# stmbluepill2.net
KiCad netlist of a schematic drawn in EAGLE
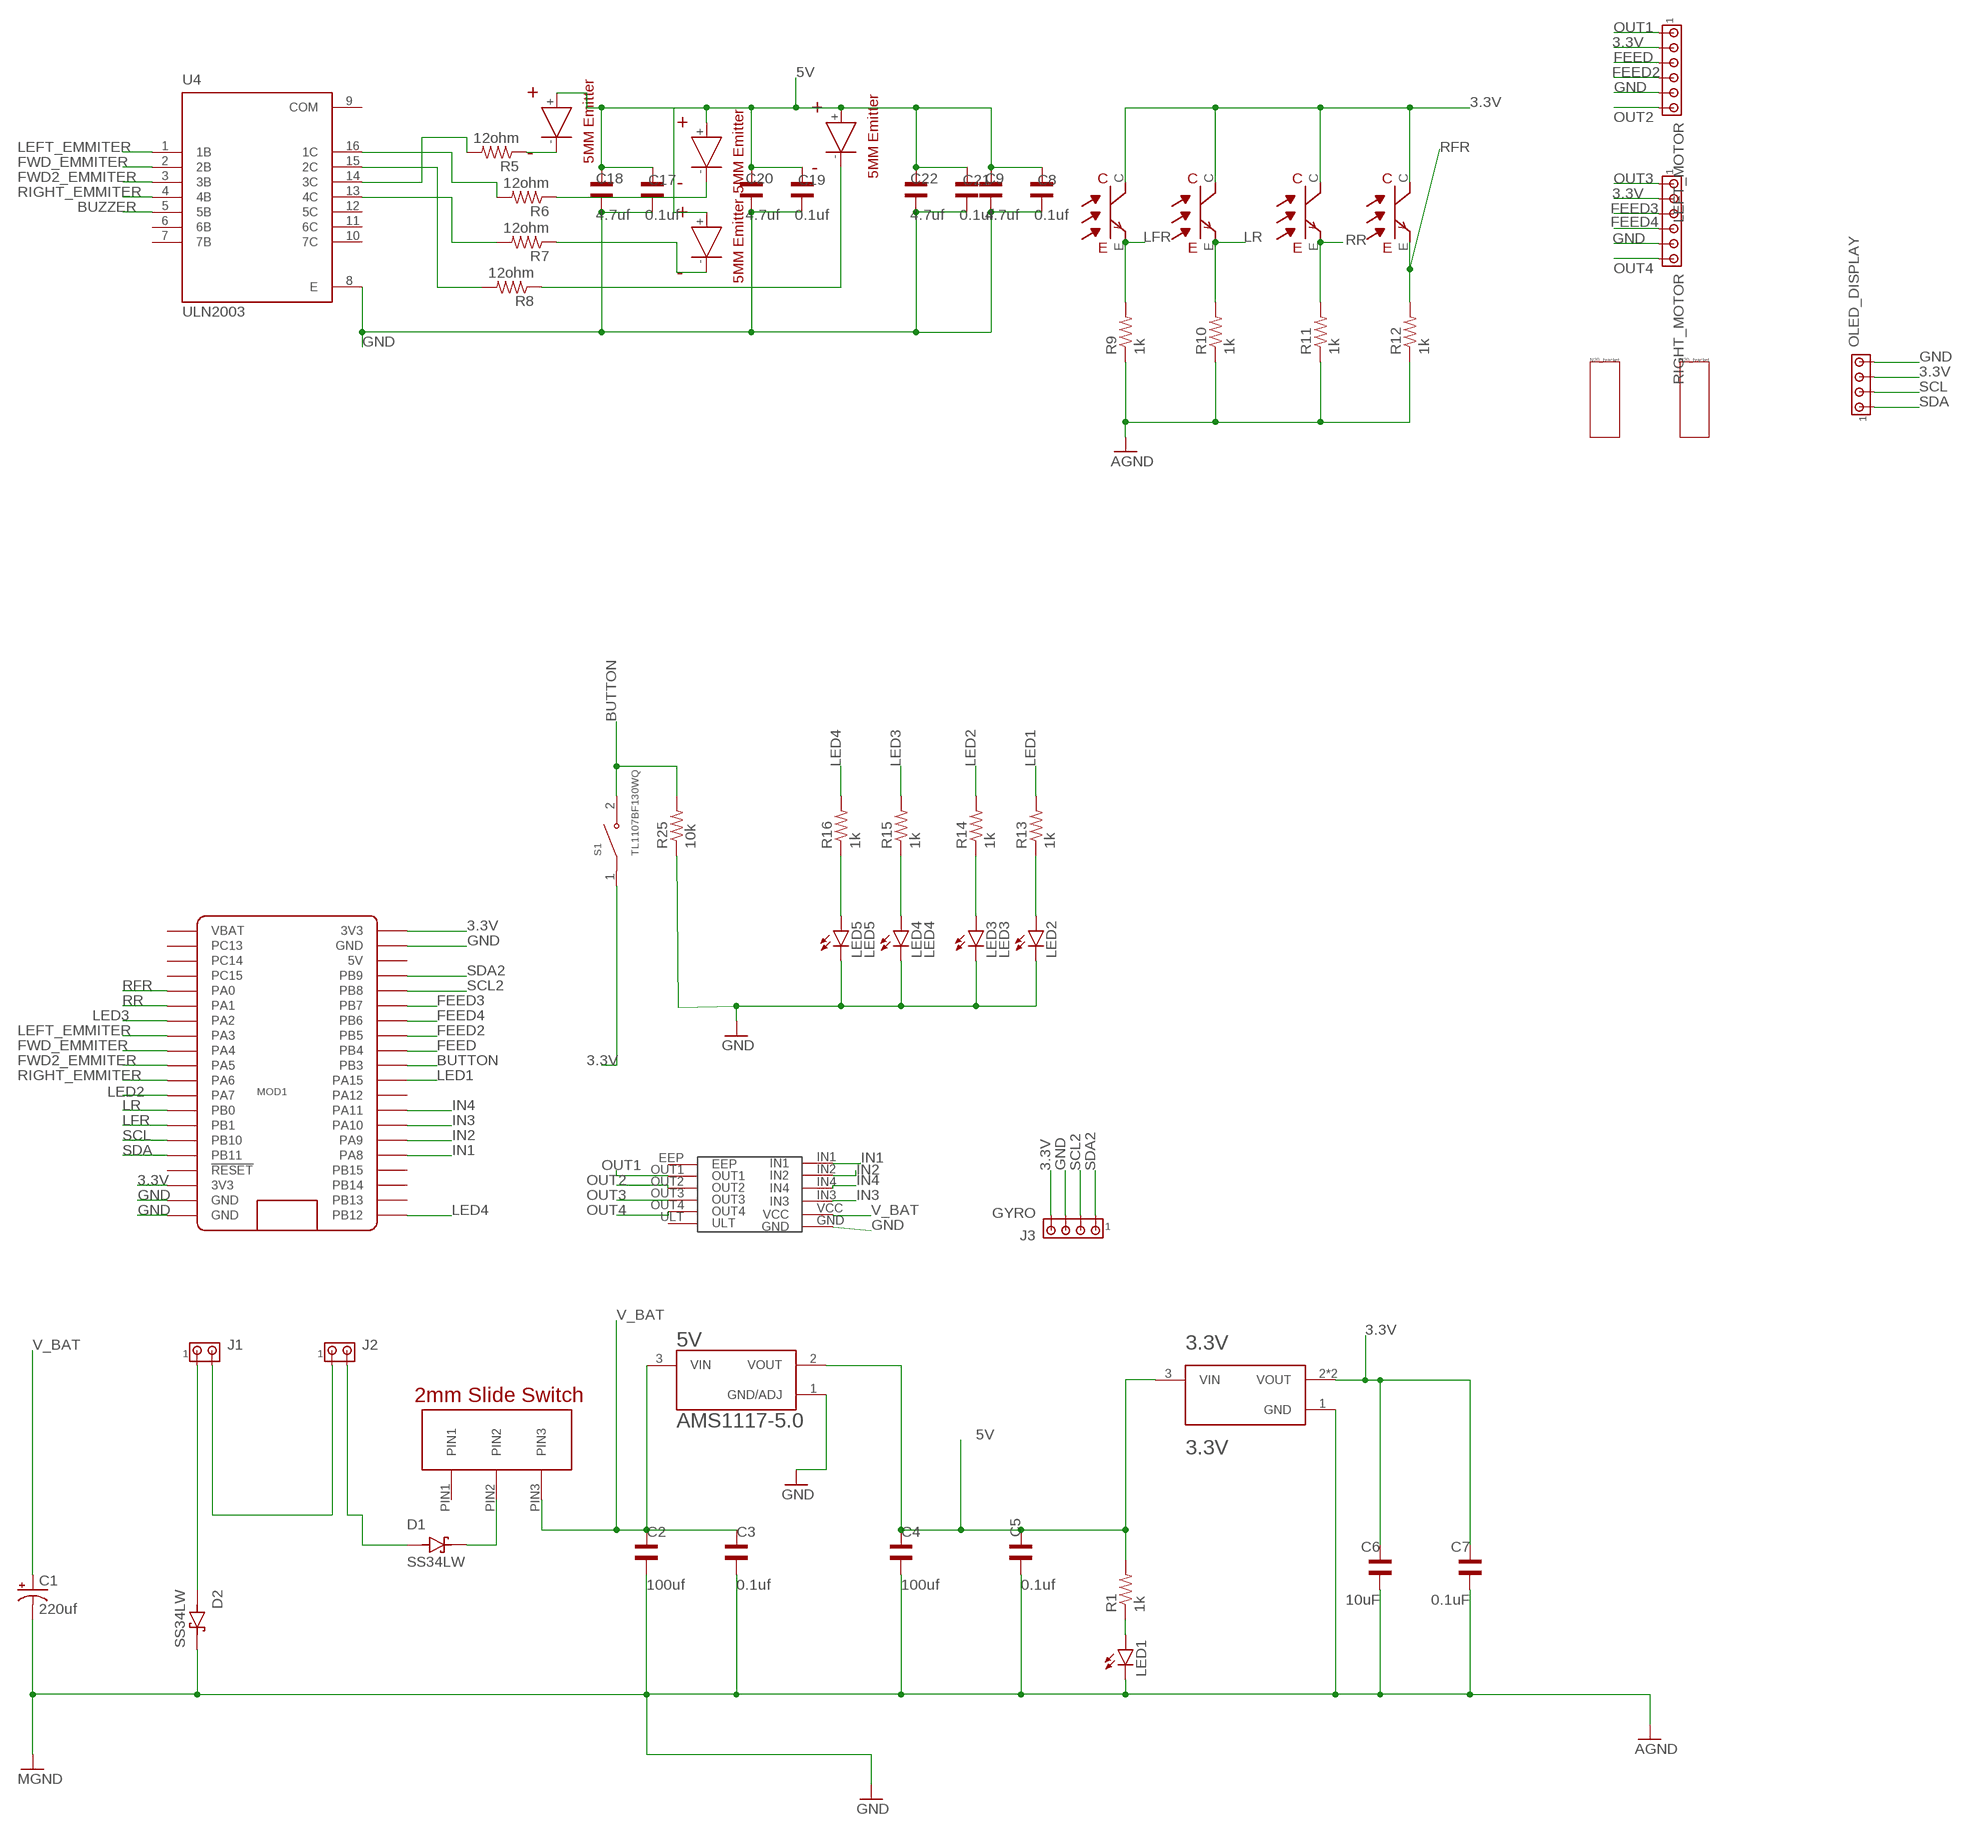
[diagram p0: schematic, sheet 1]

(export (version "E")
  (design (tool "Eeschema 10.0.6"))
  (components
    (comp (ref "3.3V")
      (value "3.3V")
      (footprint "eagle-import:SOT230P700X180-4N")
      (fields (field (name "MF") "STMicroelectronics") (field (name "MP") "LDL1117S33R"))
      (libsource (lib "eagle-import") (part "LDL1117S33R"))
    )
    (comp (ref "5V")
      (value "AMS1117-5.0")
      (footprint "eagle-import:SOT229P700X180-4N")
      (fields (field (name "MF") "Advanced Monolithic Systems"))
      (libsource (lib "eagle-import") (part "AMS1117-5.0"))
    )
    (comp (ref "C1")
      (value "220uf")
      (footprint "eagle-import:EIA3216")
      (libsource (lib "eagle-import") (part "CAP_POL1206"))
    )
    (comp (ref "C2")
      (value "100uf")
      (footprint "eagle-import:WCAP-CSGP_885012206026")
      (fields (field (name "MF") "Würth Elektronik") (field (name "MP") "885012206026"))
      (libsource (lib "eagle-import") (part "885012206026"))
    )
    (comp (ref "C3")
      (value "0.1uf")
      (footprint "eagle-import:WCAP-CSGP_885012206026")
      (fields (field (name "MF") "Würth Elektronik") (field (name "MP") "885012206026"))
      (libsource (lib "eagle-import") (part "885012206026"))
    )
    (comp (ref "C4")
      (value "100uf")
      (footprint "eagle-import:WCAP-CSGP_885012206026")
      (fields (field (name "MF") "Würth Elektronik") (field (name "MP") "885012206026"))
      (libsource (lib "eagle-import") (part "885012206026"))
    )
    (comp (ref "C5")
      (value "0.1uf")
      (footprint "eagle-import:WCAP-CSGP_885012206026")
      (fields (field (name "MF") "Würth Elektronik") (field (name "MP") "885012206026"))
      (libsource (lib "eagle-import") (part "885012206026"))
    )
    (comp (ref "C6")
      (value "10uF")
      (footprint "eagle-import:WCAP-CSGP_885012206026")
      (fields (field (name "MF") "Würth Elektronik") (field (name "MP") "885012206026"))
      (libsource (lib "eagle-import") (part "885012206026"))
    )
    (comp (ref "C7")
      (value "0.1uF")
      (footprint "eagle-import:WCAP-CSGP_885012206026")
      (fields (field (name "MF") "Würth Elektronik") (field (name "MP") "885012206026"))
      (libsource (lib "eagle-import") (part "885012206026"))
    )
    (comp (ref "C8")
      (value "0.1uf")
      (footprint "eagle-import:WCAP-CSGP_885012206026")
      (fields (field (name "MF") "Würth Elektronik") (field (name "MP") "885012206026"))
      (libsource (lib "eagle-import") (part "885012206026"))
    )
    (comp (ref "C9")
      (value "4.7uf")
      (footprint "eagle-import:WCAP-CSGP_885012206026")
      (fields (field (name "MF") "Würth Elektronik") (field (name "MP") "885012206026"))
      (libsource (lib "eagle-import") (part "885012206026"))
    )
    (comp (ref "C17")
      (value "0.1uf")
      (footprint "eagle-import:WCAP-CSGP_885012206026")
      (fields (field (name "MF") "Würth Elektronik") (field (name "MP") "885012206026"))
      (libsource (lib "eagle-import") (part "885012206026"))
    )
    (comp (ref "C18")
      (value "4.7uf")
      (footprint "eagle-import:WCAP-CSGP_885012206026")
      (fields (field (name "MF") "Würth Elektronik") (field (name "MP") "885012206026"))
      (libsource (lib "eagle-import") (part "885012206026"))
    )
    (comp (ref "C19")
      (value "0.1uf")
      (footprint "eagle-import:WCAP-CSGP_885012206026")
      (fields (field (name "MF") "Würth Elektronik") (field (name "MP") "885012206026"))
      (libsource (lib "eagle-import") (part "885012206026"))
    )
    (comp (ref "C20")
      (value "4.7uf")
      (footprint "eagle-import:WCAP-CSGP_885012206026")
      (fields (field (name "MF") "Würth Elektronik") (field (name "MP") "885012206026"))
      (libsource (lib "eagle-import") (part "885012206026"))
    )
    (comp (ref "C21")
      (value "0.1uf")
      (footprint "eagle-import:WCAP-CSGP_885012206026")
      (fields (field (name "MF") "Würth Elektronik") (field (name "MP") "885012206026"))
      (libsource (lib "eagle-import") (part "885012206026"))
    )
    (comp (ref "C22")
      (value "4.7uf")
      (footprint "eagle-import:WCAP-CSGP_885012206026")
      (fields (field (name "MF") "Würth Elektronik") (field (name "MP") "885012206026"))
      (libsource (lib "eagle-import") (part "885012206026"))
    )
    (comp (ref "D1")
      (value "SS34LW")
      (footprint "eagle-import:SODFL3718X102N")
      (fields (field (name "MF") "Taiwan Semiconductor"))
      (libsource (lib "eagle-import") (part "SS34LW"))
    )
    (comp (ref "D2")
      (value "SS34LW")
      (footprint "eagle-import:SODFL3718X102N")
      (fields (field (name "MF") "Taiwan Semiconductor"))
      (libsource (lib "eagle-import") (part "SS34LW"))
    )
    (comp (ref "EMMI1")
      (value "EMITTER")
      (footprint "eagle-import:EMITTER")
      (libsource (lib "eagle-import") (part "EMITTER"))
    )
    (comp (ref "J1")
      (value "MTA02-100")
      (footprint "eagle-import:10X02MTA")
      (libsource (lib "eagle-import") (part "MTA02-100"))
    )
    (comp (ref "J2")
      (value "MTA02-100")
      (footprint "eagle-import:10X02MTA")
      (libsource (lib "eagle-import") (part "MTA02-100"))
    )
    (comp (ref "J3")
      (value "GYRO")
      (footprint "eagle-import:10X04MTA")
      (libsource (lib "eagle-import") (part "MTA04-100"))
    )
    (comp (ref "LED1")
      (value "LEDCHIPLED_0805")
      (footprint "eagle-import:CHIPLED_0805")
      (libsource (lib "eagle-import") (part "LEDCHIPLED_0805"))
    )
    (comp (ref "LED2")
      (value "LEDCHIPLED_0805")
      (footprint "eagle-import:CHIPLED_0805")
      (libsource (lib "eagle-import") (part "LEDCHIPLED_0805"))
    )
    (comp (ref "LED3")
      (value "LED3")
      (footprint "eagle-import:CHIPLED_0805")
      (libsource (lib "eagle-import") (part "LEDCHIPLED_0805"))
    )
    (comp (ref "LED4")
      (value "LED4")
      (footprint "eagle-import:CHIPLED_0805")
      (libsource (lib "eagle-import") (part "LEDCHIPLED_0805"))
    )
    (comp (ref "LED5")
      (value "LED5")
      (footprint "eagle-import:CHIPLED_0805")
      (libsource (lib "eagle-import") (part "LEDCHIPLED_0805"))
    )
    (comp (ref "LEFT_MOTOR")
      (value "MTA06-100")
      (footprint "eagle-import:10X06MTA")
      (libsource (lib "eagle-import") (part "MTA06-100"))
    )
    (comp (ref "MOD1")
      (value "BLUE_PILLADVANCED")
      (footprint "eagle-import:BLUE_PILL_ADV")
      (libsource (lib "eagle-import") (part "BLUE_PILLADVANCED"))
    )
    (comp (ref "OLED_DISPLAY")
      (value "MTA04-100")
      (footprint "eagle-import:10X04MTA")
      (libsource (lib "eagle-import") (part "MTA04-100"))
    )
    (comp (ref "R1")
      (value "1k")
      (footprint "eagle-import:0603-RES")
      (libsource (lib "eagle-import") (part "RESISTOR0603-RES"))
    )
    (comp (ref "R5")
      (value "12ohm")
      (footprint "eagle-import:0603-RES")
      (libsource (lib "eagle-import") (part "RESISTOR0603-RES"))
    )
    (comp (ref "R6")
      (value "12ohm")
      (footprint "eagle-import:0603-RES")
      (libsource (lib "eagle-import") (part "RESISTOR0603-RES"))
    )
    (comp (ref "R7")
      (value "12ohm")
      (footprint "eagle-import:0603-RES")
      (libsource (lib "eagle-import") (part "RESISTOR0603-RES"))
    )
    (comp (ref "R8")
      (value "12ohm")
      (footprint "eagle-import:0603-RES")
      (libsource (lib "eagle-import") (part "RESISTOR0603-RES"))
    )
    (comp (ref "R9")
      (value "1k")
      (footprint "eagle-import:0603-RES")
      (libsource (lib "eagle-import") (part "RESISTOR0603-RES"))
    )
    (comp (ref "R10")
      (value "1k")
      (footprint "eagle-import:0603-RES")
      (libsource (lib "eagle-import") (part "RESISTOR0603-RES"))
    )
    (comp (ref "R11")
      (value "1k")
      (footprint "eagle-import:0603-RES")
      (libsource (lib "eagle-import") (part "RESISTOR0603-RES"))
    )
    (comp (ref "R12")
      (value "1k")
      (footprint "eagle-import:0603-RES")
      (libsource (lib "eagle-import") (part "RESISTOR0603-RES"))
    )
    (comp (ref "R13")
      (value "1k")
      (footprint "eagle-import:0603-RES")
      (libsource (lib "eagle-import") (part "RESISTOR0603-RES"))
    )
    (comp (ref "R14")
      (value "1k")
      (footprint "eagle-import:0603-RES")
      (libsource (lib "eagle-import") (part "RESISTOR0603-RES"))
    )
    (comp (ref "R15")
      (value "1k")
      (footprint "eagle-import:0603-RES")
      (libsource (lib "eagle-import") (part "RESISTOR0603-RES"))
    )
    (comp (ref "R16")
      (value "1k")
      (footprint "eagle-import:0603-RES")
      (libsource (lib "eagle-import") (part "RESISTOR0603-RES"))
    )
    (comp (ref "R25")
      (value "10k")
      (footprint "eagle-import:0603-RES")
      (libsource (lib "eagle-import") (part "RESISTOR0603-RES"))
    )
    (comp (ref "RIGHT_MOTOR")
      (value "MTA06-100")
      (footprint "eagle-import:10X06MTA")
      (libsource (lib "eagle-import") (part "MTA06-100"))
    )
    (comp (ref "S1")
      (value "TL1107BF130WQ")
      (footprint "eagle-import:SW_TL1107BF130WQ")
      (fields (field (name "MF") "E-Switch"))
      (libsource (lib "eagle-import") (part "TL1107BF130WQ"))
    )
    (comp (ref "U$1")
      (value "N20_BRACKET")
      (footprint "eagle-import:BRACKER")
      (libsource (lib "eagle-import") (part "N20_BRACKET"))
    )
    (comp (ref "U$4")
      (value "N20_BRACKET")
      (footprint "eagle-import:BRACKER")
      (libsource (lib "eagle-import") (part "N20_BRACKET"))
    )
    (comp (ref "U$8")
      (value "2MMS_SLIDE_SWITCH")
      (footprint "eagle-import:2MMS_SLIDE_SWITCH")
      (libsource (lib "eagle-import") (part "2MMS_SLIDE_SWITCH"))
    )
    (comp (ref "U$11")
      (value "DRV8833")
      (footprint "eagle-import:DRV8833")
      (libsource (lib "eagle-import") (part "DRV8833"))
    )
    (comp (ref "U$12")
      (value "RECEIVER")
      (footprint "eagle-import:RECEIVER")
      (libsource (lib "eagle-import") (part "RECEIVER"))
    )
    (comp (ref "U$13")
      (value "EMITTER")
      (footprint "eagle-import:EMITTER")
      (libsource (lib "eagle-import") (part "EMITTER"))
    )
    (comp (ref "U$14")
      (value "EMITTER")
      (footprint "eagle-import:EMITTER")
      (libsource (lib "eagle-import") (part "EMITTER"))
    )
    (comp (ref "U$15")
      (value "EMITTER")
      (footprint "eagle-import:EMITTER")
      (libsource (lib "eagle-import") (part "EMITTER"))
    )
    (comp (ref "U$16")
      (value "RECEIVER")
      (footprint "eagle-import:RECEIVER")
      (libsource (lib "eagle-import") (part "RECEIVER"))
    )
    (comp (ref "U$17")
      (value "RECEIVER")
      (footprint "eagle-import:RECEIVER")
      (libsource (lib "eagle-import") (part "RECEIVER"))
    )
    (comp (ref "U$18")
      (value "RECEIVER")
      (footprint "eagle-import:RECEIVER")
      (libsource (lib "eagle-import") (part "RECEIVER"))
    )
    (comp (ref "U4")
      (value "ULN2003")
      (footprint "eagle-import:SOP65P640X120-16N")
      (fields (field (name "MF") "Texas Instruments") (field (name "MP") "ULN2003APWR"))
      (libsource (lib "eagle-import") (part "ULN2003APWR"))
    )
  )
  (nets
    (net (code "1") (name "/3.3V") (class "Default")
      (node (ref "3.3V") (pin "2") (pinfunction "VOUT_2") (pintype "output"))
      (node (ref "3.3V") (pin "4") (pinfunction "VOUT_4") (pintype "output"))
      (node (ref "C6") (pin "2") (pinfunction "2_2") (pintype "passive"))
      (node (ref "C7") (pin "2") (pinfunction "2_2") (pintype "passive"))
      (node (ref "J3") (pin "4") (pinfunction "4_4") (pintype "passive"))
      (node (ref "LEFT_MOTOR") (pin "2") (pinfunction "2_2") (pintype "passive"))
      (node (ref "MOD1") (pin "P$20") (pinfunction "3V3_P$20") (pintype "bidirectional"))
      (node (ref "MOD1") (pin "P$23") (pinfunction "3V3_P$23") (pintype "bidirectional"))
      (node (ref "OLED_DISPLAY") (pin "3") (pinfunction "3_3") (pintype "passive"))
      (node (ref "RIGHT_MOTOR") (pin "2") (pinfunction "2_2") (pintype "passive"))
      (node (ref "S1") (pin "1") (pinfunction "1_1") (pintype "passive"))
      (node (ref "U$12") (pin "C") (pinfunction "C_C") (pintype "bidirectional"))
      (node (ref "U$16") (pin "C") (pinfunction "C_C") (pintype "bidirectional"))
      (node (ref "U$17") (pin "C") (pinfunction "C_C") (pintype "bidirectional"))
      (node (ref "U$18") (pin "C") (pinfunction "C_C") (pintype "bidirectional"))
    )
    (net (code "2") (name "/5V") (class "Default")
      (node (ref "3.3V") (pin "3") (pinfunction "VIN_3") (pintype "input"))
      (node (ref "5V") (pin "2") (pinfunction "VOUT_2") (pintype "output"))
      (node (ref "C17") (pin "2") (pinfunction "2_2") (pintype "passive"))
      (node (ref "C18") (pin "2") (pinfunction "2_2") (pintype "passive"))
      (node (ref "C19") (pin "2") (pinfunction "2_2") (pintype "passive"))
      (node (ref "C20") (pin "2") (pinfunction "2_2") (pintype "passive"))
      (node (ref "C21") (pin "2") (pinfunction "2_2") (pintype "passive"))
      (node (ref "C22") (pin "2") (pinfunction "2_2") (pintype "passive"))
      (node (ref "C4") (pin "2") (pinfunction "2_2") (pintype "passive"))
      (node (ref "C5") (pin "2") (pinfunction "2_2") (pintype "passive"))
      (node (ref "C8") (pin "2") (pinfunction "2_2") (pintype "passive"))
      (node (ref "C9") (pin "2") (pinfunction "2_2") (pintype "passive"))
      (node (ref "EMMI1") (pin "+") (pinfunction "+_+") (pintype "bidirectional"))
      (node (ref "R1") (pin "2") (pinfunction "2_2") (pintype "passive"))
      (node (ref "U$13") (pin "+") (pinfunction "+_+") (pintype "bidirectional"))
      (node (ref "U$14") (pin "+") (pinfunction "+_+") (pintype "bidirectional"))
      (node (ref "U$15") (pin "+") (pinfunction "+_+") (pintype "bidirectional"))
    )
    (net (code "3") (name "/BUTTON") (class "Default")
      (node (ref "MOD1") (pin "P$11") (pinfunction "PB3_P$11") (pintype "bidirectional"))
      (node (ref "R25") (pin "2") (pinfunction "2_2") (pintype "passive"))
      (node (ref "S1") (pin "2") (pinfunction "2_2") (pintype "passive"))
    )
    (net (code "4") (name "/BUZZER") (class "Default")
      (node (ref "U4") (pin "5") (pinfunction "5B_5") (pintype "input"))
    )
    (net (code "5") (name "/COM") (class "Default")
      (node (ref "U4") (pin "9") (pinfunction "COM_9") (pintype "power_in"))
    )
    (net (code "6") (name "/FEED") (class "Default")
      (node (ref "LEFT_MOTOR") (pin "3") (pinfunction "3_3") (pintype "passive"))
      (node (ref "MOD1") (pin "P$12") (pinfunction "PB4_P$12") (pintype "bidirectional"))
    )
    (net (code "7") (name "/FEED2") (class "Default")
      (node (ref "LEFT_MOTOR") (pin "4") (pinfunction "4_4") (pintype "passive"))
      (node (ref "MOD1") (pin "P$13") (pinfunction "PB5_P$13") (pintype "bidirectional"))
    )
    (net (code "8") (name "/FEED3") (class "Default")
      (node (ref "MOD1") (pin "P$15") (pinfunction "PB7_P$15") (pintype "bidirectional"))
      (node (ref "RIGHT_MOTOR") (pin "3") (pinfunction "3_3") (pintype "passive"))
    )
    (net (code "9") (name "/FEED4") (class "Default")
      (node (ref "MOD1") (pin "P$14") (pinfunction "PB6_P$14") (pintype "bidirectional"))
      (node (ref "RIGHT_MOTOR") (pin "4") (pinfunction "4_4") (pintype "passive"))
    )
    (net (code "10") (name "/FWD2_EMMITER") (class "Default")
      (node (ref "MOD1") (pin "P$31") (pinfunction "PA5_P$31") (pintype "bidirectional"))
      (node (ref "U4") (pin "3") (pinfunction "3B_3") (pintype "input"))
    )
    (net (code "11") (name "/FWD_EMMITER") (class "Default")
      (node (ref "MOD1") (pin "P$32") (pinfunction "PA4_P$32") (pintype "bidirectional"))
      (node (ref "U4") (pin "2") (pinfunction "2B_2") (pintype "input"))
    )
    (net (code "12") (name "/IN1") (class "Default")
      (node (ref "MOD1") (pin "P$5") (pinfunction "PA8_P$5") (pintype "bidirectional"))
      (node (ref "U$11") (pin "IN1") (pinfunction "IN1_IN1") (pintype "bidirectional"))
    )
    (net (code "13") (name "/IN2") (class "Default")
      (node (ref "MOD1") (pin "P$6") (pinfunction "PA9_P$6") (pintype "bidirectional"))
      (node (ref "U$11") (pin "IN2") (pinfunction "IN2_IN2") (pintype "bidirectional"))
    )
    (net (code "14") (name "/IN3") (class "Default")
      (node (ref "MOD1") (pin "P$7") (pinfunction "PA10_P$7") (pintype "bidirectional"))
      (node (ref "U$11") (pin "IN3") (pinfunction "IN3_IN3") (pintype "bidirectional"))
    )
    (net (code "15") (name "/IN4") (class "Default")
      (node (ref "MOD1") (pin "P$8") (pinfunction "PA11_P$8") (pintype "bidirectional"))
      (node (ref "U$11") (pin "IN4") (pinfunction "IN4_IN4") (pintype "bidirectional"))
    )
    (net (code "16") (name "/LED1") (class "Default")
      (node (ref "MOD1") (pin "P$10") (pinfunction "PA15_P$10") (pintype "bidirectional"))
      (node (ref "R13") (pin "2") (pinfunction "2_2") (pintype "passive"))
    )
    (net (code "17") (name "/LED2") (class "Default")
      (node (ref "MOD1") (pin "P$29") (pinfunction "PA7_P$29") (pintype "bidirectional"))
      (node (ref "R14") (pin "2") (pinfunction "2_2") (pintype "passive"))
    )
    (net (code "18") (name "/LED3") (class "Default")
      (node (ref "MOD1") (pin "P$34") (pinfunction "PA2_P$34") (pintype "bidirectional"))
      (node (ref "R15") (pin "2") (pinfunction "2_2") (pintype "passive"))
    )
    (net (code "19") (name "/LED4") (class "Default")
      (node (ref "MOD1") (pin "P$1") (pinfunction "PB12_P$1") (pintype "bidirectional"))
      (node (ref "R16") (pin "2") (pinfunction "2_2") (pintype "passive"))
    )
    (net (code "20") (name "/LEFT_EMMITER") (class "Default")
      (node (ref "MOD1") (pin "P$33") (pinfunction "PA3_P$33") (pintype "bidirectional"))
      (node (ref "U4") (pin "1") (pinfunction "1B_1") (pintype "input"))
    )
    (net (code "21") (name "/LFR") (class "Default")
      (node (ref "MOD1") (pin "P$27") (pinfunction "PB1_P$27") (pintype "bidirectional"))
      (node (ref "R9") (pin "2") (pinfunction "2_2") (pintype "passive"))
      (node (ref "U$18") (pin "E") (pinfunction "E_E") (pintype "bidirectional"))
    )
    (net (code "22") (name "/LR") (class "Default")
      (node (ref "MOD1") (pin "P$28") (pinfunction "PB0_P$28") (pintype "bidirectional"))
      (node (ref "R10") (pin "2") (pinfunction "2_2") (pintype "passive"))
      (node (ref "U$17") (pin "E") (pinfunction "E_E") (pintype "bidirectional"))
    )
    (net (code "23") (name "/OUT1") (class "Default")
      (node (ref "LEFT_MOTOR") (pin "1") (pinfunction "1_1") (pintype "passive"))
      (node (ref "U$11") (pin "OUT1") (pinfunction "OUT1_OUT1") (pintype "bidirectional"))
    )
    (net (code "24") (name "/OUT2") (class "Default")
      (node (ref "LEFT_MOTOR") (pin "6") (pinfunction "6_6") (pintype "passive"))
      (node (ref "U$11") (pin "OUT2") (pinfunction "OUT2_OUT2") (pintype "bidirectional"))
    )
    (net (code "25") (name "/OUT3") (class "Default")
      (node (ref "RIGHT_MOTOR") (pin "1") (pinfunction "1_1") (pintype "passive"))
      (node (ref "U$11") (pin "OUT3") (pinfunction "OUT3_OUT3") (pintype "bidirectional"))
    )
    (net (code "26") (name "/OUT4") (class "Default")
      (node (ref "RIGHT_MOTOR") (pin "6") (pinfunction "6_6") (pintype "passive"))
      (node (ref "U$11") (pin "OUT4") (pinfunction "OUT4_OUT4") (pintype "bidirectional"))
    )
    (net (code "27") (name "/RFR") (class "Default")
      (node (ref "MOD1") (pin "P$36") (pinfunction "PA0_P$36") (pintype "bidirectional"))
      (node (ref "R12") (pin "2") (pinfunction "2_2") (pintype "passive"))
      (node (ref "U$12") (pin "E") (pinfunction "E_E") (pintype "bidirectional"))
    )
    (net (code "28") (name "/RIGHT_EMMITER") (class "Default")
      (node (ref "MOD1") (pin "P$30") (pinfunction "PA6_P$30") (pintype "bidirectional"))
      (node (ref "U4") (pin "4") (pinfunction "4B_4") (pintype "input"))
    )
    (net (code "29") (name "/RR") (class "Default")
      (node (ref "MOD1") (pin "P$35") (pinfunction "PA1_P$35") (pintype "bidirectional"))
      (node (ref "R11") (pin "2") (pinfunction "2_2") (pintype "passive"))
      (node (ref "U$16") (pin "E") (pinfunction "E_E") (pintype "bidirectional"))
    )
    (net (code "30") (name "/SCL") (class "Default")
      (node (ref "MOD1") (pin "P$26") (pinfunction "PB10_P$26") (pintype "bidirectional"))
      (node (ref "OLED_DISPLAY") (pin "2") (pinfunction "2_2") (pintype "passive"))
    )
    (net (code "31") (name "/SCL2") (class "Default")
      (node (ref "J3") (pin "2") (pinfunction "2_2") (pintype "passive"))
      (node (ref "MOD1") (pin "P$16") (pinfunction "PB8_P$16") (pintype "bidirectional"))
    )
    (net (code "32") (name "/SDA") (class "Default")
      (node (ref "MOD1") (pin "P$25") (pinfunction "PB11_P$25") (pintype "bidirectional"))
      (node (ref "OLED_DISPLAY") (pin "1") (pinfunction "1_1") (pintype "passive"))
    )
    (net (code "33") (name "/SDA2") (class "Default")
      (node (ref "J3") (pin "1") (pinfunction "1_1") (pintype "passive"))
      (node (ref "MOD1") (pin "P$17") (pinfunction "PB9_P$17") (pintype "bidirectional"))
    )
    (net (code "34") (name "/V_BAT") (class "Default")
      (node (ref "5V") (pin "3") (pinfunction "VIN_3") (pintype "input"))
      (node (ref "C1") (pin "A") (pinfunction "+_A") (pintype "passive"))
      (node (ref "C2") (pin "2") (pinfunction "2_2") (pintype "passive"))
      (node (ref "C3") (pin "2") (pinfunction "2_2") (pintype "passive"))
      (node (ref "U$11") (pin "VCC") (pinfunction "VCC_VCC") (pintype "bidirectional"))
      (node (ref "U$8") (pin "PIN3") (pinfunction "PIN3_PIN3") (pintype "bidirectional"))
    )
    (net (code "35") (name "AGND") (class "Default")
      (node (ref "3.3V") (pin "1") (pinfunction "GND_1") (pintype "power_in"))
      (node (ref "5V") (pin "1") (pinfunction "GND/ADJ_1") (pintype "power_in"))
      (node (ref "C1") (pin "C") (pinfunction "-_C") (pintype "passive"))
      (node (ref "C17") (pin "1") (pinfunction "1_1") (pintype "passive"))
      (node (ref "C18") (pin "1") (pinfunction "1_1") (pintype "passive"))
      (node (ref "C19") (pin "1") (pinfunction "1_1") (pintype "passive"))
      (node (ref "C2") (pin "1") (pinfunction "1_1") (pintype "passive"))
      (node (ref "C20") (pin "1") (pinfunction "1_1") (pintype "passive"))
      (node (ref "C21") (pin "1") (pinfunction "1_1") (pintype "passive"))
      (node (ref "C22") (pin "1") (pinfunction "1_1") (pintype "passive"))
      (node (ref "C3") (pin "1") (pinfunction "1_1") (pintype "passive"))
      (node (ref "C4") (pin "1") (pinfunction "1_1") (pintype "passive"))
      (node (ref "C5") (pin "1") (pinfunction "1_1") (pintype "passive"))
      (node (ref "C6") (pin "1") (pinfunction "1_1") (pintype "passive"))
      (node (ref "C7") (pin "1") (pinfunction "1_1") (pintype "passive"))
      (node (ref "C8") (pin "1") (pinfunction "1_1") (pintype "passive"))
      (node (ref "C9") (pin "1") (pinfunction "1_1") (pintype "passive"))
      (node (ref "D2") (pin "C") (pinfunction "K_C") (pintype "passive"))
      (node (ref "J3") (pin "3") (pinfunction "3_3") (pintype "passive"))
      (node (ref "LED1") (pin "C") (pinfunction "C_C") (pintype "passive"))
      (node (ref "LED2") (pin "C") (pinfunction "C_C") (pintype "passive"))
      (node (ref "LED3") (pin "C") (pinfunction "C_C") (pintype "passive"))
      (node (ref "LED4") (pin "C") (pinfunction "C_C") (pintype "passive"))
      (node (ref "LED5") (pin "C") (pinfunction "C_C") (pintype "passive"))
      (node (ref "LEFT_MOTOR") (pin "5") (pinfunction "5_5") (pintype "passive"))
      (node (ref "MOD1") (pin "P$19") (pinfunction "GND_P$19") (pintype "passive"))
      (node (ref "MOD1") (pin "P$21") (pinfunction "GND_P$21") (pintype "passive"))
      (node (ref "MOD1") (pin "P$22") (pinfunction "GND_P$22") (pintype "passive"))
      (node (ref "OLED_DISPLAY") (pin "4") (pinfunction "4_4") (pintype "passive"))
      (node (ref "R10") (pin "1") (pinfunction "1_1") (pintype "passive"))
      (node (ref "R11") (pin "1") (pinfunction "1_1") (pintype "passive"))
      (node (ref "R12") (pin "1") (pinfunction "1_1") (pintype "passive"))
      (node (ref "R25") (pin "1") (pinfunction "1_1") (pintype "passive"))
      (node (ref "R9") (pin "1") (pinfunction "1_1") (pintype "passive"))
      (node (ref "RIGHT_MOTOR") (pin "5") (pinfunction "5_5") (pintype "passive"))
      (node (ref "U$11") (pin "GND") (pinfunction "GND_GND") (pintype "bidirectional"))
      (node (ref "U4") (pin "8") (pinfunction "E_8") (pintype "power_in"))
    )
    (net (code "36") (name "Net-(D1-K)") (class "Default")
      (node (ref "D1") (pin "C") (pinfunction "K_C") (pintype "passive"))
      (node (ref "U$8") (pin "PIN2") (pinfunction "PIN2_PIN2") (pintype "bidirectional"))
    )
    (net (code "37") (name "Net-(D1-PadA)") (class "Default")
      (node (ref "D1") (pin "A") (pinfunction "A_A") (pintype "passive"))
      (node (ref "J2") (pin "2") (pinfunction "2_2") (pintype "passive"))
    )
    (net (code "38") (name "Net-(D2-PadA)") (class "Default")
      (node (ref "D2") (pin "A") (pinfunction "A_A") (pintype "passive"))
      (node (ref "J1") (pin "1") (pinfunction "1_1") (pintype "passive"))
    )
    (net (code "39") (name "Net-(EMMI1-Pad-)") (class "Default")
      (node (ref "EMMI1") (pin "-") (pinfunction "-_-") (pintype "bidirectional"))
      (node (ref "R5") (pin "1") (pinfunction "1_1") (pintype "passive"))
    )
    (net (code "40") (name "Net-(J1-Pad2)") (class "Default")
      (node (ref "J1") (pin "2") (pinfunction "2_2") (pintype "passive"))
      (node (ref "J2") (pin "1") (pinfunction "1_1") (pintype "passive"))
    )
    (net (code "41") (name "Net-(LED1-PadA)") (class "Default")
      (node (ref "LED1") (pin "A") (pinfunction "A_A") (pintype "passive"))
      (node (ref "R1") (pin "1") (pinfunction "1_1") (pintype "passive"))
    )
    (net (code "42") (name "Net-(LED2-PadA)") (class "Default")
      (node (ref "LED2") (pin "A") (pinfunction "A_A") (pintype "passive"))
      (node (ref "R13") (pin "1") (pinfunction "1_1") (pintype "passive"))
    )
    (net (code "43") (name "Net-(LED3-PadA)") (class "Default")
      (node (ref "LED3") (pin "A") (pinfunction "A_A") (pintype "passive"))
      (node (ref "R14") (pin "1") (pinfunction "1_1") (pintype "passive"))
    )
    (net (code "44") (name "Net-(LED4-PadA)") (class "Default")
      (node (ref "LED4") (pin "A") (pinfunction "A_A") (pintype "passive"))
      (node (ref "R15") (pin "1") (pinfunction "1_1") (pintype "passive"))
    )
    (net (code "45") (name "Net-(LED5-PadA)") (class "Default")
      (node (ref "LED5") (pin "A") (pinfunction "A_A") (pintype "passive"))
      (node (ref "R16") (pin "1") (pinfunction "1_1") (pintype "passive"))
    )
    (net (code "46") (name "Net-(R6-Pad1)") (class "Default")
      (node (ref "R6") (pin "1") (pinfunction "1_1") (pintype "passive"))
      (node (ref "U$13") (pin "-") (pinfunction "-_-") (pintype "bidirectional"))
    )
    (net (code "47") (name "Net-(R7-Pad1)") (class "Default")
      (node (ref "R7") (pin "1") (pinfunction "1_1") (pintype "passive"))
      (node (ref "U$14") (pin "-") (pinfunction "-_-") (pintype "bidirectional"))
    )
    (net (code "48") (name "Net-(R8-Pad1)") (class "Default")
      (node (ref "R8") (pin "1") (pinfunction "1_1") (pintype "passive"))
      (node (ref "U$15") (pin "-") (pinfunction "-_-") (pintype "bidirectional"))
    )
    (net (code "49") (name "Net-(U4-1C)") (class "Default")
      (node (ref "R6") (pin "2") (pinfunction "2_2") (pintype "passive"))
      (node (ref "U4") (pin "16") (pinfunction "1C_16") (pintype "output"))
    )
    (net (code "50") (name "Net-(U4-2C)") (class "Default")
      (node (ref "R8") (pin "2") (pinfunction "2_2") (pintype "passive"))
      (node (ref "U4") (pin "15") (pinfunction "2C_15") (pintype "output"))
    )
    (net (code "51") (name "Net-(U4-3C)") (class "Default")
      (node (ref "R5") (pin "2") (pinfunction "2_2") (pintype "passive"))
      (node (ref "U4") (pin "14") (pinfunction "3C_14") (pintype "output"))
    )
    (net (code "52") (name "Net-(U4-4C)") (class "Default")
      (node (ref "R7") (pin "2") (pinfunction "2_2") (pintype "passive"))
      (node (ref "U4") (pin "13") (pinfunction "4C_13") (pintype "output"))
    )
    (net (code "53") (name "unconnected-(MOD1-5V-PadP$18)") (class "Default")
      (node (ref "MOD1") (pin "P$18") (pinfunction "5V_P$18") (pintype "bidirectional"))
    )
    (net (code "54") (name "unconnected-(MOD1-PA12-PadP$9)") (class "Default")
      (node (ref "MOD1") (pin "P$9") (pinfunction "PA12_P$9") (pintype "bidirectional"))
    )
    (net (code "55") (name "unconnected-(MOD1-PB13-PadP$2)") (class "Default")
      (node (ref "MOD1") (pin "P$2") (pinfunction "PB13_P$2") (pintype "bidirectional"))
    )
    (net (code "56") (name "unconnected-(MOD1-PB14-PadP$3)") (class "Default")
      (node (ref "MOD1") (pin "P$3") (pinfunction "PB14_P$3") (pintype "bidirectional"))
    )
    (net (code "57") (name "unconnected-(MOD1-PB15-PadP$4)") (class "Default")
      (node (ref "MOD1") (pin "P$4") (pinfunction "PB15_P$4") (pintype "bidirectional"))
    )
    (net (code "58") (name "unconnected-(MOD1-PC13-PadP$39)") (class "Default")
      (node (ref "MOD1") (pin "P$39") (pinfunction "PC13_P$39") (pintype "bidirectional"))
    )
    (net (code "59") (name "unconnected-(MOD1-PC14-PadP$38)") (class "Default")
      (node (ref "MOD1") (pin "P$38") (pinfunction "PC14_P$38") (pintype "bidirectional"))
    )
    (net (code "60") (name "unconnected-(MOD1-PC15-PadP$37)") (class "Default")
      (node (ref "MOD1") (pin "P$37") (pinfunction "PC15_P$37") (pintype "bidirectional"))
    )
    (net (code "61") (name "unconnected-(MOD1-VBAT-PadP$40)") (class "Default")
      (node (ref "MOD1") (pin "P$40") (pinfunction "VBAT_P$40") (pintype "bidirectional"))
    )
    (net (code "62") (name "unconnected-(MOD1-~{RESET}-PadP$24)") (class "Default")
      (node (ref "MOD1") (pin "P$24") (pinfunction "~{RESET}_P$24") (pintype "bidirectional"))
    )
    (net (code "63") (name "unconnected-(U$8-PadPIN1)") (class "Default")
      (node (ref "U$8") (pin "PIN1") (pinfunction "PIN1_PIN1") (pintype "bidirectional"))
    )
    (net (code "64") (name "unconnected-(U$11-PadEEP)") (class "Default")
      (node (ref "U$11") (pin "EEP") (pinfunction "EEP_EEP") (pintype "bidirectional"))
    )
    (net (code "65") (name "unconnected-(U$11-PadULT)") (class "Default")
      (node (ref "U$11") (pin "ULT") (pinfunction "ULT_ULT") (pintype "bidirectional"))
    )
    (net (code "66") (name "unconnected-(U4-5C-Pad12)") (class "Default")
      (node (ref "U4") (pin "12") (pinfunction "5C_12") (pintype "output"))
    )
    (net (code "67") (name "unconnected-(U4-6B-Pad6)") (class "Default")
      (node (ref "U4") (pin "6") (pinfunction "6B_6") (pintype "input"))
    )
    (net (code "68") (name "unconnected-(U4-6C-Pad11)") (class "Default")
      (node (ref "U4") (pin "11") (pinfunction "6C_11") (pintype "output"))
    )
    (net (code "69") (name "unconnected-(U4-7B-Pad7)") (class "Default")
      (node (ref "U4") (pin "7") (pinfunction "7B_7") (pintype "input"))
    )
    (net (code "70") (name "unconnected-(U4-7C-Pad10)") (class "Default")
      (node (ref "U4") (pin "10") (pinfunction "7C_10") (pintype "output"))
    )
  )
)
